# LEDMatrix.net
KiCad netlist of a schematic drawn in EAGLE
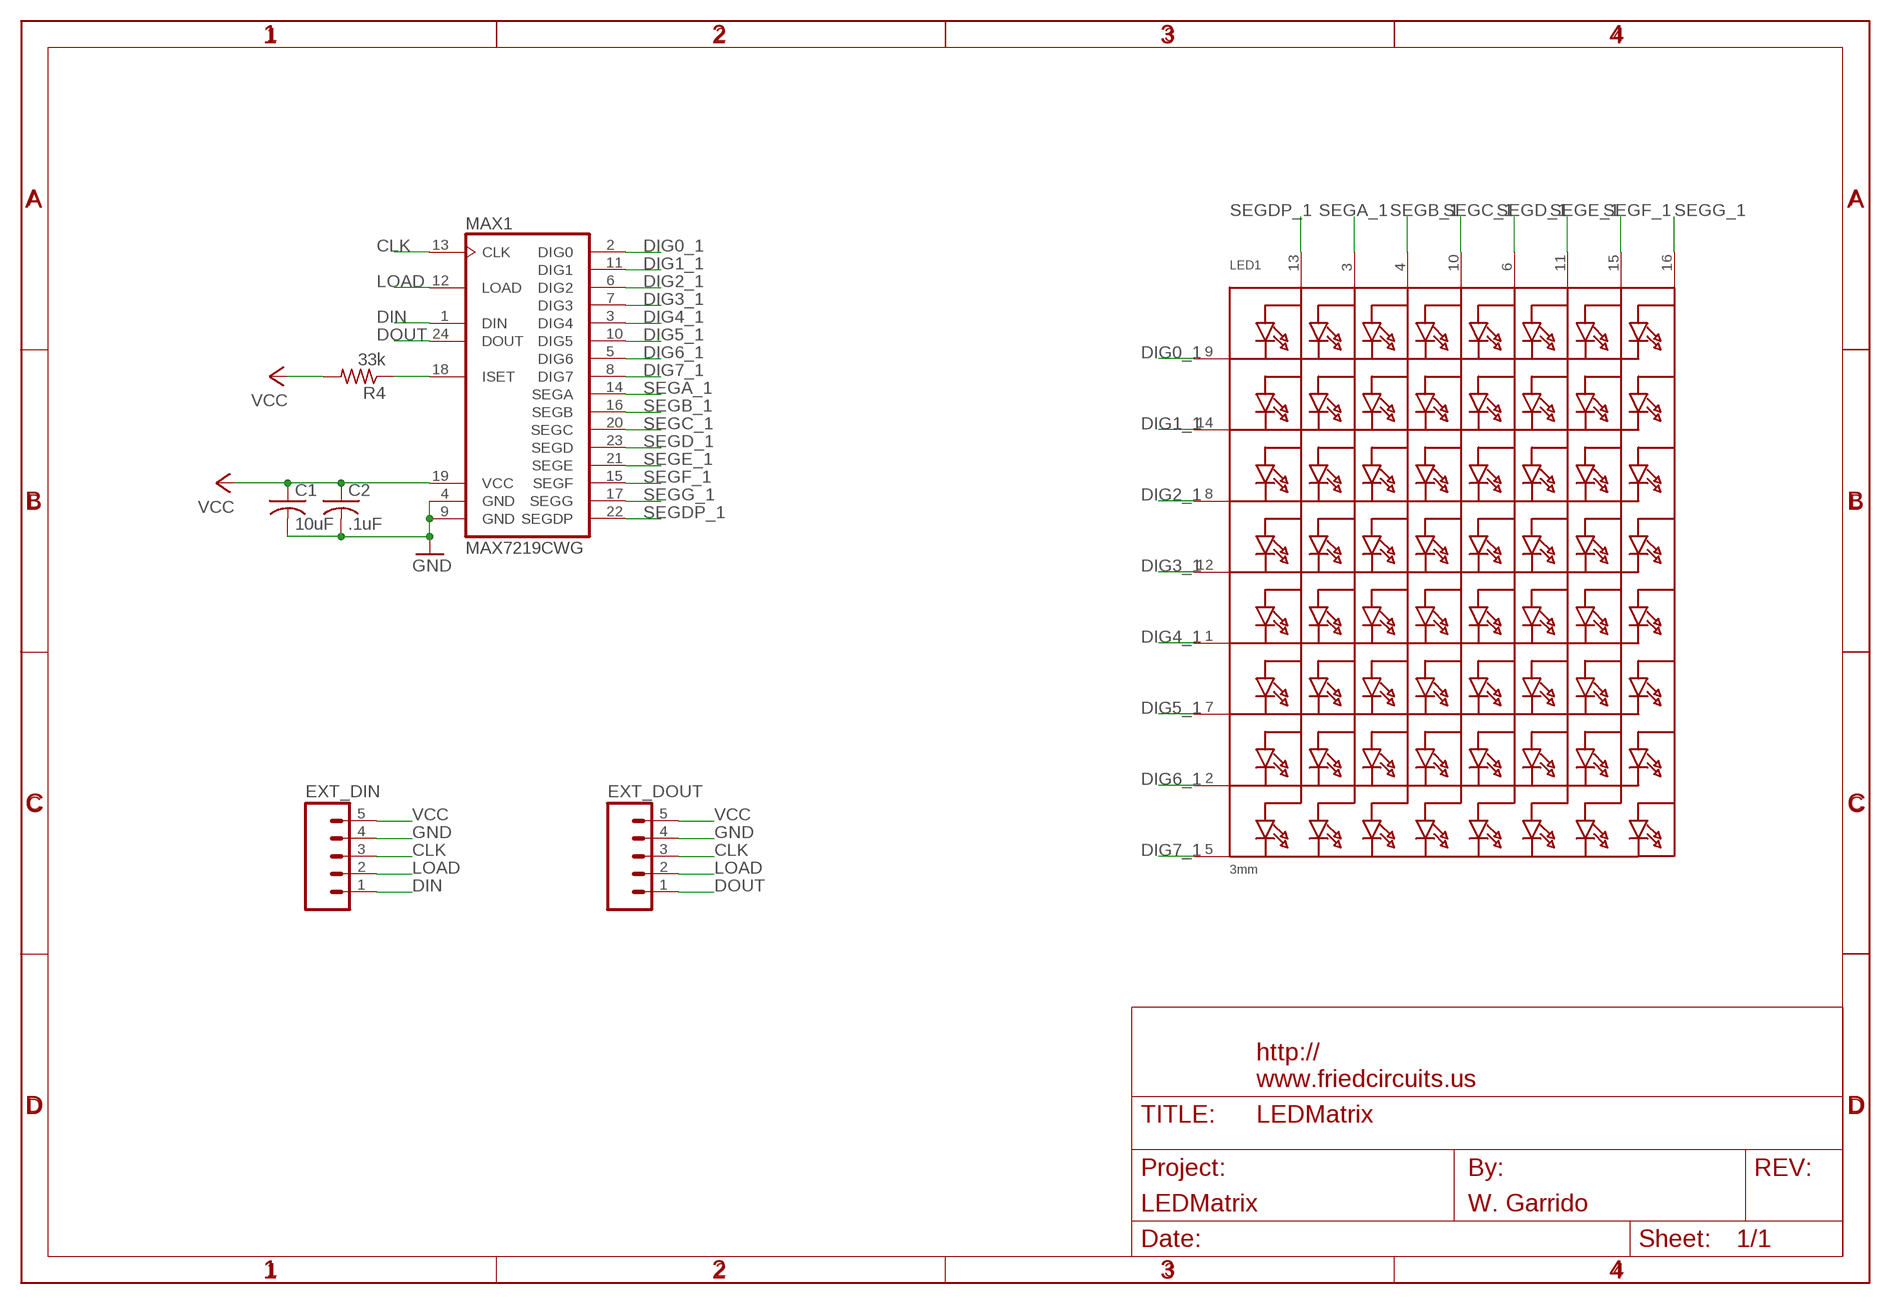
[diagram p0: schematic, sheet 1]

(export (version "E")
  (design (tool "Eeschema 10.0.6"))
  (components
    (comp (ref "C1")
      (value "10uF")
      (footprint "eagle-import:C0805")
      (libsource (lib "eagle-import") (part "C-USC0805"))
    )
    (comp (ref "C2")
      (value ".1uF")
      (footprint "eagle-import:C0805")
      (libsource (lib "eagle-import") (part "C-USC0805"))
    )
    (comp (ref "EXT_DIN")
      (value "M05LOCK_LONGPADS")
      (footprint "eagle-import:1X05_LOCK_LONGPADS")
      (libsource (lib "eagle-import") (part "M05LOCK_LONGPADS"))
    )
    (comp (ref "EXT_DOUT")
      (value "M05LOCK_LONGPADS")
      (footprint "eagle-import:1X05_LOCK_LONGPADS")
      (libsource (lib "eagle-import") (part "M05LOCK_LONGPADS"))
    )
    (comp (ref "LED1")
      (value "3mm")
      (footprint "eagle-import:SEGMENT_BL-M12A881UR")
      (libsource (lib "eagle-import") (part "SEGMENT_8X8_ROWCATHODEM12A881UR"))
    )
    (comp (ref "MAX1")
      (value "MAX7219CWG")
      (footprint "eagle-import:SO24W")
      (libsource (lib "eagle-import") (part "MAX7219WGC"))
    )
    (comp (ref "R4")
      (value "33k")
      (footprint "eagle-import:M0805")
      (libsource (lib "eagle-import") (part "R-US_M0805"))
    )
    (comp (ref "U$1")
      (value "FRAME_DINA4_L")
      (footprint "eagle-import:FC_CREDIT")
      (fields (field (name "PROJECT") "LEDMatrix") (field (name "AUTHOR") "W. Garrido"))
      (libsource (lib "eagle-import") (part "FRAME_DINA4_L"))
    )
  )
  (nets
    (net (code "1") (name "/CLK") (class "Default")
      (node (ref "EXT_DIN") (pin "3") (pinfunction "3_3") (pintype "passive"))
      (node (ref "EXT_DOUT") (pin "3") (pinfunction "3_3") (pintype "passive"))
      (node (ref "MAX1") (pin "13") (pinfunction "CLK_13") (pintype "input"))
    )
    (net (code "2") (name "/DIG0_1") (class "Default")
      (node (ref "LED1") (pin "9") (pinfunction "K1_9") (pintype "bidirectional"))
      (node (ref "MAX1") (pin "2") (pinfunction "DIG0_2") (pintype "output"))
    )
    (net (code "3") (name "/DIG1_1") (class "Default")
      (node (ref "LED1") (pin "14") (pinfunction "K2_14") (pintype "bidirectional"))
      (node (ref "MAX1") (pin "11") (pinfunction "DIG1_11") (pintype "output"))
    )
    (net (code "4") (name "/DIG2_1") (class "Default")
      (node (ref "LED1") (pin "8") (pinfunction "K3_8") (pintype "bidirectional"))
      (node (ref "MAX1") (pin "6") (pinfunction "DIG2_6") (pintype "output"))
    )
    (net (code "5") (name "/DIG3_1") (class "Default")
      (node (ref "LED1") (pin "12") (pinfunction "K4_12") (pintype "bidirectional"))
      (node (ref "MAX1") (pin "7") (pinfunction "DIG3_7") (pintype "output"))
    )
    (net (code "6") (name "/DIG4_1") (class "Default")
      (node (ref "LED1") (pin "1") (pinfunction "K5_1") (pintype "bidirectional"))
      (node (ref "MAX1") (pin "3") (pinfunction "DIG4_3") (pintype "output"))
    )
    (net (code "7") (name "/DIG5_1") (class "Default")
      (node (ref "LED1") (pin "7") (pinfunction "K6_7") (pintype "bidirectional"))
      (node (ref "MAX1") (pin "10") (pinfunction "DIG5_10") (pintype "output"))
    )
    (net (code "8") (name "/DIG6_1") (class "Default")
      (node (ref "LED1") (pin "2") (pinfunction "K7_2") (pintype "bidirectional"))
      (node (ref "MAX1") (pin "5") (pinfunction "DIG6_5") (pintype "output"))
    )
    (net (code "9") (name "/DIG7_1") (class "Default")
      (node (ref "LED1") (pin "5") (pinfunction "K8_5") (pintype "bidirectional"))
      (node (ref "MAX1") (pin "8") (pinfunction "DIG7_8") (pintype "output"))
    )
    (net (code "10") (name "/DIN") (class "Default")
      (node (ref "EXT_DIN") (pin "1") (pinfunction "1_1") (pintype "passive"))
      (node (ref "MAX1") (pin "1") (pinfunction "DIN_1") (pintype "input"))
    )
    (net (code "11") (name "/DOUT") (class "Default")
      (node (ref "EXT_DOUT") (pin "1") (pinfunction "1_1") (pintype "passive"))
      (node (ref "MAX1") (pin "24") (pinfunction "DOUT_24") (pintype "output"))
    )
    (net (code "12") (name "/LOAD") (class "Default")
      (node (ref "EXT_DIN") (pin "2") (pinfunction "2_2") (pintype "passive"))
      (node (ref "EXT_DOUT") (pin "2") (pinfunction "2_2") (pintype "passive"))
      (node (ref "MAX1") (pin "12") (pinfunction "LOAD_12") (pintype "input"))
    )
    (net (code "13") (name "/SEGA_1") (class "Default")
      (node (ref "LED1") (pin "3") (pinfunction "A2_3") (pintype "bidirectional"))
      (node (ref "MAX1") (pin "14") (pinfunction "SEGA_14") (pintype "output"))
    )
    (net (code "14") (name "/SEGB_1") (class "Default")
      (node (ref "LED1") (pin "4") (pinfunction "A3_4") (pintype "bidirectional"))
      (node (ref "MAX1") (pin "16") (pinfunction "SEGB_16") (pintype "output"))
    )
    (net (code "15") (name "/SEGC_1") (class "Default")
      (node (ref "LED1") (pin "10") (pinfunction "A4_10") (pintype "bidirectional"))
      (node (ref "MAX1") (pin "20") (pinfunction "SEGC_20") (pintype "output"))
    )
    (net (code "16") (name "/SEGDP_1") (class "Default")
      (node (ref "LED1") (pin "13") (pinfunction "A1_13") (pintype "bidirectional"))
      (node (ref "MAX1") (pin "22") (pinfunction "SEGDP_22") (pintype "output"))
    )
    (net (code "17") (name "/SEGD_1") (class "Default")
      (node (ref "LED1") (pin "6") (pinfunction "A5_6") (pintype "bidirectional"))
      (node (ref "MAX1") (pin "23") (pinfunction "SEGD_23") (pintype "output"))
    )
    (net (code "18") (name "/SEGE_1") (class "Default")
      (node (ref "LED1") (pin "11") (pinfunction "A6_11") (pintype "bidirectional"))
      (node (ref "MAX1") (pin "21") (pinfunction "SEGE_21") (pintype "output"))
    )
    (net (code "19") (name "/SEGF_1") (class "Default")
      (node (ref "LED1") (pin "15") (pinfunction "A7_15") (pintype "bidirectional"))
      (node (ref "MAX1") (pin "15") (pinfunction "SEGF_15") (pintype "output"))
    )
    (net (code "20") (name "/SEGG_1") (class "Default")
      (node (ref "LED1") (pin "16") (pinfunction "A8_16") (pintype "bidirectional"))
      (node (ref "MAX1") (pin "17") (pinfunction "SEGG_17") (pintype "output"))
    )
    (net (code "21") (name "GND") (class "Default")
      (node (ref "C1") (pin "2") (pinfunction "2_2") (pintype "passive"))
      (node (ref "C2") (pin "2") (pinfunction "2_2") (pintype "passive"))
      (node (ref "EXT_DIN") (pin "4") (pinfunction "4_4") (pintype "passive"))
      (node (ref "EXT_DOUT") (pin "4") (pinfunction "4_4") (pintype "passive"))
      (node (ref "MAX1") (pin "4") (pinfunction "GND_4") (pintype "power_in"))
      (node (ref "MAX1") (pin "9") (pinfunction "GND_9") (pintype "power_in"))
    )
    (net (code "22") (name "Net-(MAX1-ISET)") (class "Default")
      (node (ref "MAX1") (pin "18") (pinfunction "ISET_18") (pintype "input"))
      (node (ref "R4") (pin "1") (pinfunction "1_1") (pintype "passive"))
    )
    (net (code "23") (name "VCC") (class "Default")
      (node (ref "C1") (pin "1") (pinfunction "1_1") (pintype "passive"))
      (node (ref "C2") (pin "1") (pinfunction "1_1") (pintype "passive"))
      (node (ref "EXT_DIN") (pin "5") (pinfunction "5_5") (pintype "passive"))
      (node (ref "EXT_DOUT") (pin "5") (pinfunction "5_5") (pintype "passive"))
      (node (ref "MAX1") (pin "19") (pinfunction "VCC_19") (pintype "power_in"))
      (node (ref "R4") (pin "2") (pinfunction "2_2") (pintype "passive"))
    )
  )
)
